# Sheet1.net
KiCad netlist of a schematic drawn in Altium Designer
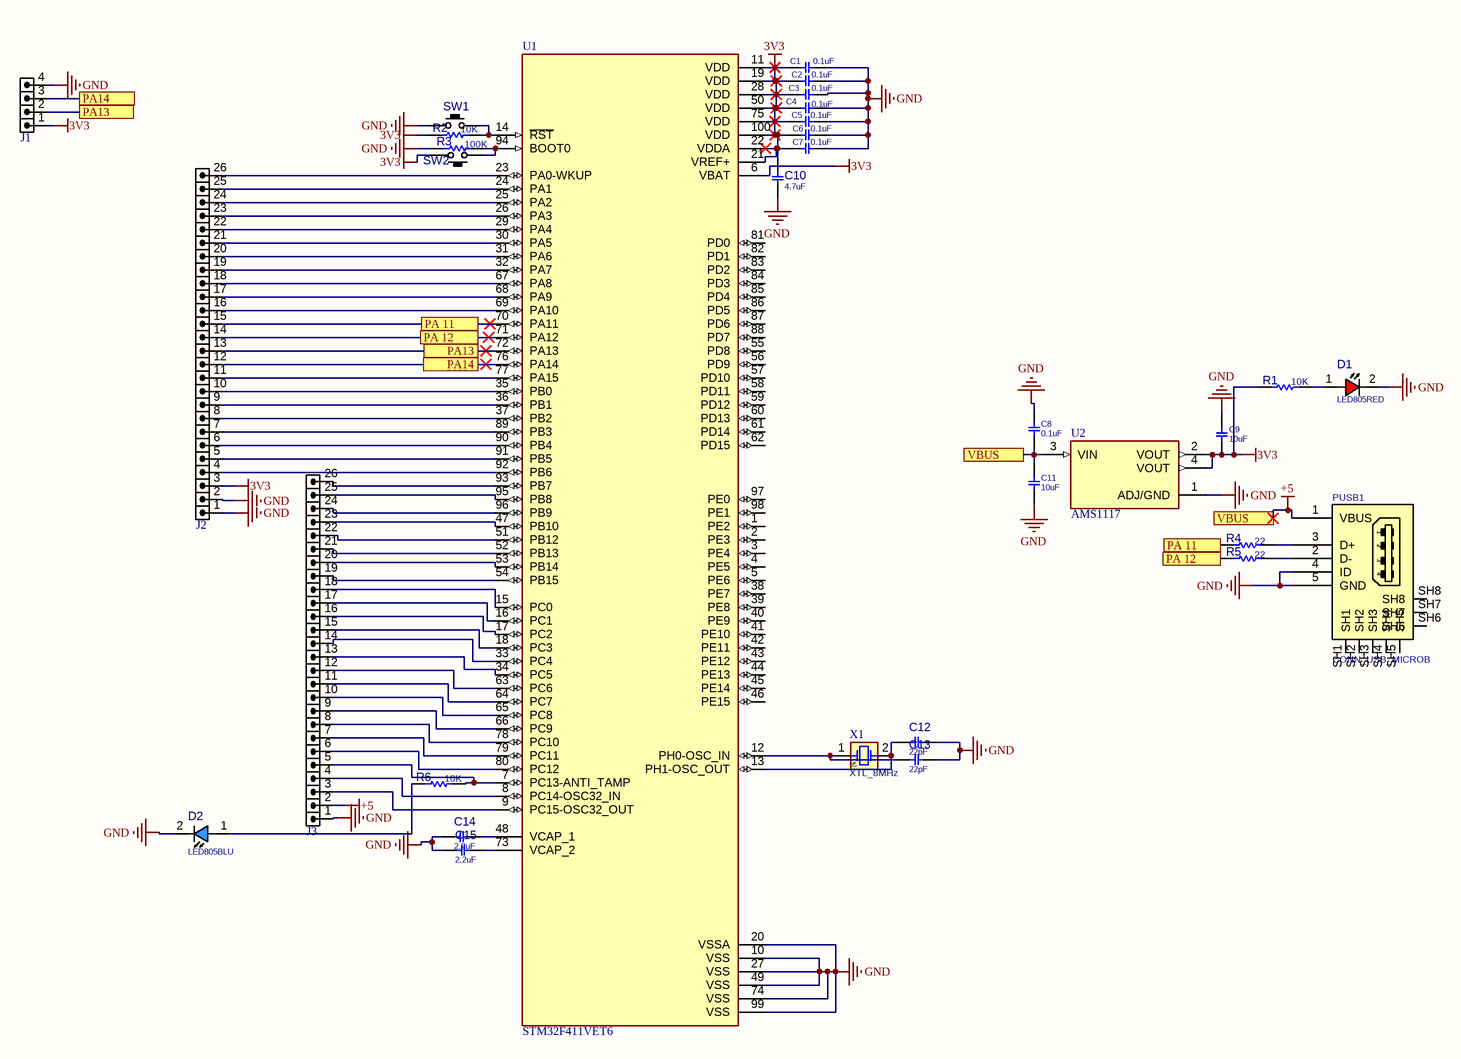
[diagram p0: Sheet1.SchDoc]

(export (version "E")
  (design (tool "Eeschema 10.0.6"))
  (components
    (comp (ref "C1")
      (value "0.1uF")
      (footprint "C0402")
      (description "CAP, MLCC, 100nF, 50V, X5R, 10%, 0402C")
      (fields (field (name "MANF_P#") "UMK105BJ104KV-F") (field (name "MANF") "Taiyo Yuden"))
      (libsource (lib "Custom") (part "CAP_SMD_MLCC_100n50T"))
    )
    (comp (ref "C2")
      (value "0.1uF")
      (footprint "C0402")
      (description "CAP, MLCC, 100nF, 50V, X5R, 10%, 0402C")
      (fields (field (name "MANF_P#") "UMK105BJ104KV-F") (field (name "MANF") "Taiyo Yuden"))
      (libsource (lib "Custom") (part "CAP_SMD_MLCC_100n50T"))
    )
    (comp (ref "C3")
      (value "0.1uF")
      (footprint "C0402")
      (description "CAP, MLCC, 100nF, 50V, X5R, 10%, 0402C")
      (fields (field (name "MANF_P#") "UMK105BJ104KV-F") (field (name "MANF") "Taiyo Yuden"))
      (libsource (lib "Custom") (part "CAP_SMD_MLCC_100n50T"))
    )
    (comp (ref "C4")
      (value "0.1uF")
      (footprint "C0402")
      (description "CAP, MLCC, 100nF, 50V, X5R, 10%, 0402C")
      (fields (field (name "MANF_P#") "UMK105BJ104KV-F") (field (name "MANF") "Taiyo Yuden"))
      (libsource (lib "Custom") (part "CAP_SMD_MLCC_100n50T"))
    )
    (comp (ref "C5")
      (value "0.1uF")
      (footprint "C0402")
      (description "CAP, MLCC, 100nF, 50V, X5R, 10%, 0402C")
      (fields (field (name "MANF_P#") "UMK105BJ104KV-F") (field (name "MANF") "Taiyo Yuden"))
      (libsource (lib "Custom") (part "CAP_SMD_MLCC_100n50T"))
    )
    (comp (ref "C6")
      (value "0.1uF")
      (footprint "C0402")
      (description "CAP, MLCC, 100nF, 50V, X5R, 10%, 0402C")
      (fields (field (name "MANF_P#") "UMK105BJ104KV-F") (field (name "MANF") "Taiyo Yuden"))
      (libsource (lib "Custom") (part "CAP_SMD_MLCC_100n50T"))
    )
    (comp (ref "C7")
      (value "0.1uF")
      (footprint "C0402")
      (description "CAP, MLCC, 100nF, 50V, X5R, 10%, 0402C")
      (fields (field (name "MANF_P#") "UMK105BJ104KV-F") (field (name "MANF") "Taiyo Yuden"))
      (libsource (lib "Custom") (part "CAP_SMD_MLCC_100n50T"))
    )
    (comp (ref "C8")
      (value "0.1uF")
      (footprint "C0402")
      (description "CAP, MLCC, 100nF, 50V, X5R, 10%, 0402C")
      (fields (field (name "MANF_P#") "UMK105BJ104KV-F") (field (name "MANF") "Taiyo Yuden"))
      (libsource (lib "Custom") (part "CAP_SMD_MLCC_100n50T"))
    )
    (comp (ref "C9")
      (value "10uF")
      (footprint "C0805")
      (description "CAP, MLCC, X5R 10uF 10% 25V 0805")
      (fields (field (name "MANF_P#") "TMK212BBJ106MG") (field (name "MANF") "Taiyo Yuden"))
      (libsource (lib "Custom") (part "CAP_SMD_MLCC_10u25V"))
    )
    (comp (ref "C10")
      (value "4.7uF")
      (footprint "C1206")
      (description "CAP, MLCC, SMD")
      (fields (field (name "MANF_P#") "UMK316BJ475KL-T") (field (name "MANF") "Taiyo Yuden"))
      (libsource (lib "Custom") (part "CAP_SMD_MLCC_4.7u50V"))
    )
    (comp (ref "C11")
      (value "10uF")
      (footprint "C0805")
      (description "CAP, MLCC, X5R 10uF 10% 25V 0805")
      (fields (field (name "MANF_P#") "TMK212BBJ106MG") (field (name "MANF") "Taiyo Yuden"))
      (libsource (lib "Custom") (part "CAP_SMD_MLCC_10u25V"))
    )
    (comp (ref "C12")
      (value "22pF")
      (footprint "C0402")
      (description "CAP, MLCC, 50V, C0G, 2%")
      (fields (field (name "MANF_P#") "GRM1555C1H220GA01D") (field (name "MANF") "MURATA"))
      (libsource (lib "Custom") (part "CAP_SMD_MLCC_22p50V"))
    )
    (comp (ref "C13")
      (value "22pF")
      (footprint "C0402")
      (description "CAP, MLCC, 50V, C0G, 2%")
      (fields (field (name "MANF_P#") "GRM1555C1H220GA01D") (field (name "MANF") "MURATA"))
      (libsource (lib "Custom") (part "CAP_SMD_MLCC_22p50V"))
    )
    (comp (ref "C14")
      (value "2.2uF")
      (footprint "C0805")
      (description "CAP, MLCC")
      (fields (field (name "MANF_P#") "UMK212ABJ225KG-T") (field (name "MANF") "Taiyo Yuden"))
      (libsource (lib "Custom") (part "CAP_SMD_MLCC_2.2u50V_0805"))
    )
    (comp (ref "C15")
      (value "2.2uF")
      (footprint "C0805")
      (description "CAP, MLCC")
      (fields (field (name "MANF_P#") "UMK212ABJ225KG-T") (field (name "MANF") "Taiyo Yuden"))
      (libsource (lib "Custom") (part "CAP_SMD_MLCC_2.2u50V_0805"))
    )
    (comp (ref "D1")
      (value "LED805RED")
      (footprint "LED0805RED")
      (description "LED, SMD, 0805, RED")
      (fields (field (name "MANF") "MANF") (field (name "MANF_P#") "MANF_PART#"))
      (libsource (lib "Custom") (part "LED_SMD_0805_RED"))
    )
    (comp (ref "D2")
      (value "LED805BLU")
      (footprint "LED0805BLU")
      (description "LED, SMD, 0805, BLUE")
      (fields (field (name "MANF") "MANF") (field (name "MANF_P#") "MANF_PART#"))
      (libsource (lib "Custom") (part "LED_SMD_0805_BLU"))
    )
    (comp (ref "J1")
      (value "HDR1X4")
      (footprint "HDRR_M_1X4")
      (description "CONN, HEADER, RightAngle, Male, pitch: 2.54mm, 4POS")
      (libsource (lib "Custom") (part "HDRR_M_1X4"))
    )
    (comp (ref "J2")
      (value "HDRF26")
      (footprint "HDR_M_1X26")
      (description "CONN, HEADER, Male, pitch: 2.54mm, 26POS")
      (libsource (lib "Custom") (part "HDR_M_1X26"))
    )
    (comp (ref "J3")
      (value "HDRF26")
      (footprint "HDR_M_1X26")
      (description "CONN, HEADER, Male, pitch: 2.54mm, 26POS")
      (libsource (lib "Custom") (part "HDR_M_1X26"))
    )
    (comp (ref "PUSB1")
      (value "CONN_USB_MICROB")
      (footprint "USB_MICRO_B_BM_SHT")
      (description "CONN, USB, MICRO B, R/A, SMD, BOTTOM MOUNT, SHT")
      (libsource (lib "Custom") (part "CONN_USB_MICRO_B_BM_SHT"))
    )
    (comp (ref "R1")
      (value "10K")
      (footprint "R0603")
      (description "RESISTOR, SMD")
      (libsource (lib "Custom") (part "RES_SMD_0603"))
    )
    (comp (ref "R2")
      (value "10K")
      (footprint "R0603")
      (description "RESISTOR, SMD")
      (libsource (lib "Custom") (part "RES_SMD_0603"))
    )
    (comp (ref "R3")
      (value "100K")
      (footprint "R0603")
      (description "RESISTOR, SMD")
      (libsource (lib "Custom") (part "RES_SMD_0603"))
    )
    (comp (ref "R4")
      (value "22")
      (footprint "R0603")
      (description "RESISTOR, SMD")
      (libsource (lib "Custom") (part "RES_SMD_0603"))
    )
    (comp (ref "R5")
      (value "22")
      (footprint "R0603")
      (description "RESISTOR, SMD")
      (libsource (lib "Custom") (part "RES_SMD_0603"))
    )
    (comp (ref "R6")
      (value "10K")
      (footprint "R0603")
      (description "RESISTOR, SMD")
      (libsource (lib "Custom") (part "RES_SMD_0603"))
    )
    (comp (ref "SW1")
      (value "PUSHBUTTON")
      (footprint "SWPBT_SPST_6X6X4")
      (description "SWITCH, PUSH BUTTON, TACTILE, THD, SPST, 6X6X4mm")
      (libsource (lib "") (part "SWPBT_SPST_6X6X4_1"))
    )
    (comp (ref "SW2")
      (value "PUSHBUTTON")
      (footprint "SWPBT_SPST_6X6X4")
      (description "SWITCH, PUSH BUTTON, TACTILE, THD, SPST, 6X6X4mm")
      (libsource (lib "Custom") (part "SWPBT_SPST_6X6X4"))
    )
    (comp (ref "U1")
      (value "STM32F411VET6")
      (footprint "QFP50P1600X1600X160-100N")
      (fields (field (name "MF") "STMicroelectronics") (field (name "MP") "STM32F411VET6."))
      (libsource (lib "STM32F411VET6") (part "STM32F411VET6"))
    )
    (comp (ref "U2")
      (value "AMS1117")
      (footprint "SOT229P700X180-4N")
      (description "1A LOW DROPOUT VOLTAGE REGULATOR SOT-223")
      (fields (field (name "MF") "Advanced Monolithic Systems"))
      (libsource (lib "AMS1117") (part "AMS1117"))
    )
    (comp (ref "X1")
      (value "XTL_8MHz")
      (footprint "XTL_2_8045")
      (description "Crystal 2")
      (fields (field (name "MANF") "ABRACON") (field (name "MANF_P#") "ABM2-8.000MHZ-D4Y-T"))
      (libsource (lib "Custom") (part "XTL_2_8MHz_ABM2"))
    )
  )
  (nets
    (net (code "1") (name "+5") (class "Default")
      (node (ref "C11") (pin "2") (pinfunction "2_2") (pintype "passive"))
      (node (ref "C8") (pin "1") (pinfunction "1_1") (pintype "passive"))
      (node (ref "J3") (pin "2") (pinfunction "2_2") (pintype "passive"))
      (node (ref "PUSB1") (pin "1") (pinfunction "VBUS_1") (pintype "power_in"))
      (node (ref "U2") (pin "3") (pinfunction "VIN_3") (pintype "input"))
    )
    (net (code "2") (name "/PA 11") (class "Default")
      (node (ref "J2") (pin "15") (pinfunction "15_15") (pintype "passive"))
      (node (ref "R4") (pin "1") (pinfunction "1_1") (pintype "passive"))
      (node (ref "U1") (pin "70") (pinfunction "PA11_70") (pintype "bidirectional"))
    )
    (net (code "3") (name "/PA 12") (class "Default")
      (node (ref "J2") (pin "14") (pinfunction "14_14") (pintype "passive"))
      (node (ref "R5") (pin "1") (pinfunction "1_1") (pintype "passive"))
      (node (ref "U1") (pin "71") (pinfunction "PA12_71") (pintype "bidirectional"))
    )
    (net (code "4") (name "/PA13") (class "Default")
      (node (ref "J1") (pin "2") (pinfunction "2_2") (pintype "passive"))
      (node (ref "J2") (pin "13") (pinfunction "13_13") (pintype "passive"))
      (node (ref "U1") (pin "72") (pinfunction "PA13_72") (pintype "bidirectional"))
    )
    (net (code "5") (name "/PA14") (class "Default")
      (node (ref "J1") (pin "3") (pinfunction "3_3") (pintype "passive"))
      (node (ref "J2") (pin "12") (pinfunction "12_12") (pintype "passive"))
      (node (ref "U1") (pin "76") (pinfunction "PA14_76") (pintype "bidirectional"))
    )
    (net (code "6") (name "3V3") (class "Default")
      (node (ref "C1") (pin "1") (pinfunction "1_1") (pintype "passive"))
      (node (ref "C10") (pin "2") (pinfunction "2_2") (pintype "passive"))
      (node (ref "C2") (pin "1") (pinfunction "1_1") (pintype "passive"))
      (node (ref "C3") (pin "1") (pinfunction "1_1") (pintype "passive"))
      (node (ref "C4") (pin "1") (pinfunction "1_1") (pintype "passive"))
      (node (ref "C5") (pin "1") (pinfunction "1_1") (pintype "passive"))
      (node (ref "C6") (pin "1") (pinfunction "1_1") (pintype "passive"))
      (node (ref "C7") (pin "1") (pinfunction "1_1") (pintype "passive"))
      (node (ref "C9") (pin "2") (pinfunction "2_2") (pintype "passive"))
      (node (ref "J1") (pin "1") (pinfunction "1_1") (pintype "passive"))
      (node (ref "J2") (pin "3") (pinfunction "3_3") (pintype "passive"))
      (node (ref "R1") (pin "1") (pinfunction "1_1") (pintype "passive"))
      (node (ref "R2") (pin "1") (pinfunction "1_1") (pintype "passive"))
      (node (ref "SW2") (pin "2") (pinfunction "2_2") (pintype "passive"))
      (node (ref "U1") (pin "100") (pinfunction "VDD_100") (pintype "power_in"))
      (node (ref "U1") (pin "11") (pinfunction "VDD_11") (pintype "power_in"))
      (node (ref "U1") (pin "19") (pinfunction "VDD_19") (pintype "power_in"))
      (node (ref "U1") (pin "21") (pinfunction "VREF+_21") (pintype "power_in"))
      (node (ref "U1") (pin "22") (pinfunction "VDDA_22") (pintype "power_in"))
      (node (ref "U1") (pin "28") (pinfunction "VDD_28") (pintype "power_in"))
      (node (ref "U1") (pin "50") (pinfunction "VDD_50") (pintype "power_in"))
      (node (ref "U1") (pin "6") (pinfunction "VBAT_6") (pintype "power_in"))
      (node (ref "U1") (pin "75") (pinfunction "VDD_75") (pintype "power_in"))
      (node (ref "U2") (pin "2") (pinfunction "VOUT_2") (pintype "output"))
      (node (ref "U2") (pin "4") (pinfunction "VOUT_4") (pintype "output"))
    )
    (net (code "7") (name "GND") (class "Default")
      (node (ref "C1") (pin "2") (pinfunction "2_2") (pintype "passive"))
      (node (ref "C10") (pin "1") (pinfunction "1_1") (pintype "passive"))
      (node (ref "C11") (pin "1") (pinfunction "1_1") (pintype "passive"))
      (node (ref "C12") (pin "1") (pinfunction "1_1") (pintype "passive"))
      (node (ref "C13") (pin "1") (pinfunction "1_1") (pintype "passive"))
      (node (ref "C14") (pin "1") (pinfunction "1_1") (pintype "passive"))
      (node (ref "C15") (pin "1") (pinfunction "1_1") (pintype "passive"))
      (node (ref "C2") (pin "2") (pinfunction "2_2") (pintype "passive"))
      (node (ref "C3") (pin "2") (pinfunction "2_2") (pintype "passive"))
      (node (ref "C4") (pin "2") (pinfunction "2_2") (pintype "passive"))
      (node (ref "C5") (pin "2") (pinfunction "2_2") (pintype "passive"))
      (node (ref "C6") (pin "2") (pinfunction "2_2") (pintype "passive"))
      (node (ref "C7") (pin "2") (pinfunction "2_2") (pintype "passive"))
      (node (ref "C8") (pin "2") (pinfunction "2_2") (pintype "passive"))
      (node (ref "C9") (pin "1") (pinfunction "1_1") (pintype "passive"))
      (node (ref "D1") (pin "2") (pinfunction "CATHODE_2") (pintype "passive"))
      (node (ref "D2") (pin "2") (pinfunction "CATHODE_2") (pintype "passive"))
      (node (ref "J1") (pin "4") (pinfunction "4_4") (pintype "passive"))
      (node (ref "J2") (pin "1") (pinfunction "1_1") (pintype "passive"))
      (node (ref "J2") (pin "2") (pinfunction "2_2") (pintype "passive"))
      (node (ref "J3") (pin "1") (pinfunction "1_1") (pintype "passive"))
      (node (ref "PUSB1") (pin "4") (pinfunction "ID_4") (pintype "power_in"))
      (node (ref "PUSB1") (pin "5") (pinfunction "GND_5") (pintype "power_in"))
      (node (ref "R3") (pin "1") (pinfunction "1_1") (pintype "passive"))
      (node (ref "SW1") (pin "1") (pinfunction "1_1") (pintype "passive"))
      (node (ref "U1") (pin "10") (pinfunction "VSS_10") (pintype "power_in"))
      (node (ref "U1") (pin "20") (pinfunction "VSSA_20") (pintype "power_in"))
      (node (ref "U1") (pin "27") (pinfunction "VSS_27") (pintype "power_in"))
      (node (ref "U1") (pin "49") (pinfunction "VSS_49") (pintype "power_in"))
      (node (ref "U1") (pin "74") (pinfunction "VSS_74") (pintype "power_in"))
      (node (ref "U1") (pin "99") (pinfunction "VSS_99") (pintype "power_in"))
      (node (ref "U2") (pin "1") (pinfunction "ADJ/GND_1") (pintype "power_in"))
    )
    (net (code "8") (name "Net-(D1-ANODE)") (class "Default")
      (node (ref "D1") (pin "1") (pinfunction "ANODE_1") (pintype "passive"))
      (node (ref "R1") (pin "2") (pinfunction "2_2") (pintype "passive"))
    )
    (net (code "9") (name "Net-(D2-ANODE)") (class "Default")
      (node (ref "D2") (pin "1") (pinfunction "ANODE_1") (pintype "passive"))
      (node (ref "R6") (pin "1") (pinfunction "1_1") (pintype "passive"))
    )
    (net (code "10") (name "Net-(PUSB1-D+)") (class "Default")
      (node (ref "PUSB1") (pin "3") (pinfunction "D+_3") (pintype "passive"))
      (node (ref "R4") (pin "2") (pinfunction "2_2") (pintype "passive"))
    )
    (net (code "11") (name "Net-(PUSB1-D-)") (class "Default")
      (node (ref "PUSB1") (pin "2") (pinfunction "D-_2") (pintype "passive"))
      (node (ref "R5") (pin "2") (pinfunction "2_2") (pintype "passive"))
    )
    (net (code "12") (name "Net-(U1-BOOT0)") (class "Default")
      (node (ref "R3") (pin "2") (pinfunction "2_2") (pintype "passive"))
      (node (ref "SW2") (pin "1") (pinfunction "1_1") (pintype "passive"))
      (node (ref "U1") (pin "94") (pinfunction "BOOT0_94") (pintype "input"))
    )
    (net (code "13") (name "Net-(U1-PA0-WKUP)") (class "Default")
      (node (ref "J2") (pin "26") (pinfunction "26_26") (pintype "passive"))
      (node (ref "U1") (pin "23") (pinfunction "PA0-WKUP_23") (pintype "bidirectional"))
    )
    (net (code "14") (name "Net-(U1-PA1)") (class "Default")
      (node (ref "J2") (pin "25") (pinfunction "25_25") (pintype "passive"))
      (node (ref "U1") (pin "24") (pinfunction "PA1_24") (pintype "bidirectional"))
    )
    (net (code "15") (name "Net-(U1-PA2)") (class "Default")
      (node (ref "J2") (pin "24") (pinfunction "24_24") (pintype "passive"))
      (node (ref "U1") (pin "25") (pinfunction "PA2_25") (pintype "bidirectional"))
    )
    (net (code "16") (name "Net-(U1-PA3)") (class "Default")
      (node (ref "J2") (pin "23") (pinfunction "23_23") (pintype "passive"))
      (node (ref "U1") (pin "26") (pinfunction "PA3_26") (pintype "bidirectional"))
    )
    (net (code "17") (name "Net-(U1-PA4)") (class "Default")
      (node (ref "J2") (pin "22") (pinfunction "22_22") (pintype "passive"))
      (node (ref "U1") (pin "29") (pinfunction "PA4_29") (pintype "bidirectional"))
    )
    (net (code "18") (name "Net-(U1-PA5)") (class "Default")
      (node (ref "J2") (pin "21") (pinfunction "21_21") (pintype "passive"))
      (node (ref "U1") (pin "30") (pinfunction "PA5_30") (pintype "bidirectional"))
    )
    (net (code "19") (name "Net-(U1-PA6)") (class "Default")
      (node (ref "J2") (pin "20") (pinfunction "20_20") (pintype "passive"))
      (node (ref "U1") (pin "31") (pinfunction "PA6_31") (pintype "bidirectional"))
    )
    (net (code "20") (name "Net-(U1-PA7)") (class "Default")
      (node (ref "J2") (pin "19") (pinfunction "19_19") (pintype "passive"))
      (node (ref "U1") (pin "32") (pinfunction "PA7_32") (pintype "bidirectional"))
    )
    (net (code "21") (name "Net-(U1-PA8)") (class "Default")
      (node (ref "J2") (pin "18") (pinfunction "18_18") (pintype "passive"))
      (node (ref "U1") (pin "67") (pinfunction "PA8_67") (pintype "bidirectional"))
    )
    (net (code "22") (name "Net-(U1-PA9)") (class "Default")
      (node (ref "J2") (pin "17") (pinfunction "17_17") (pintype "passive"))
      (node (ref "U1") (pin "68") (pinfunction "PA9_68") (pintype "bidirectional"))
    )
    (net (code "23") (name "Net-(U1-PA10)") (class "Default")
      (node (ref "J2") (pin "16") (pinfunction "16_16") (pintype "passive"))
      (node (ref "U1") (pin "69") (pinfunction "PA10_69") (pintype "bidirectional"))
    )
    (net (code "24") (name "Net-(U1-PA15)") (class "Default")
      (node (ref "J2") (pin "11") (pinfunction "11_11") (pintype "passive"))
      (node (ref "U1") (pin "77") (pinfunction "PA15_77") (pintype "bidirectional"))
    )
    (net (code "25") (name "Net-(U1-PB0)") (class "Default")
      (node (ref "J2") (pin "10") (pinfunction "10_10") (pintype "passive"))
      (node (ref "U1") (pin "35") (pinfunction "PB0_35") (pintype "bidirectional"))
    )
    (net (code "26") (name "Net-(U1-PB1)") (class "Default")
      (node (ref "J2") (pin "9") (pinfunction "9_9") (pintype "passive"))
      (node (ref "U1") (pin "36") (pinfunction "PB1_36") (pintype "bidirectional"))
    )
    (net (code "27") (name "Net-(U1-PB2)") (class "Default")
      (node (ref "J2") (pin "8") (pinfunction "8_8") (pintype "passive"))
      (node (ref "U1") (pin "37") (pinfunction "PB2_37") (pintype "bidirectional"))
    )
    (net (code "28") (name "Net-(U1-PB3)") (class "Default")
      (node (ref "J2") (pin "7") (pinfunction "7_7") (pintype "passive"))
      (node (ref "U1") (pin "89") (pinfunction "PB3_89") (pintype "bidirectional"))
    )
    (net (code "29") (name "Net-(U1-PB4)") (class "Default")
      (node (ref "J2") (pin "6") (pinfunction "6_6") (pintype "passive"))
      (node (ref "U1") (pin "90") (pinfunction "PB4_90") (pintype "bidirectional"))
    )
    (net (code "30") (name "Net-(U1-PB5)") (class "Default")
      (node (ref "J2") (pin "5") (pinfunction "5_5") (pintype "passive"))
      (node (ref "U1") (pin "91") (pinfunction "PB5_91") (pintype "bidirectional"))
    )
    (net (code "31") (name "Net-(U1-PB6)") (class "Default")
      (node (ref "J2") (pin "4") (pinfunction "4_4") (pintype "passive"))
      (node (ref "U1") (pin "92") (pinfunction "PB6_92") (pintype "bidirectional"))
    )
    (net (code "32") (name "Net-(U1-PB7)") (class "Default")
      (node (ref "J3") (pin "26") (pinfunction "26_26") (pintype "passive"))
      (node (ref "U1") (pin "93") (pinfunction "PB7_93") (pintype "bidirectional"))
    )
    (net (code "33") (name "Net-(U1-PB8)") (class "Default")
      (node (ref "J3") (pin "25") (pinfunction "25_25") (pintype "passive"))
      (node (ref "U1") (pin "95") (pinfunction "PB8_95") (pintype "bidirectional"))
    )
    (net (code "34") (name "Net-(U1-PB9)") (class "Default")
      (node (ref "J3") (pin "24") (pinfunction "24_24") (pintype "passive"))
      (node (ref "U1") (pin "96") (pinfunction "PB9_96") (pintype "bidirectional"))
    )
    (net (code "35") (name "Net-(U1-PB10)") (class "Default")
      (node (ref "J3") (pin "23") (pinfunction "23_23") (pintype "passive"))
      (node (ref "U1") (pin "47") (pinfunction "PB10_47") (pintype "bidirectional"))
    )
    (net (code "36") (name "Net-(U1-PB12)") (class "Default")
      (node (ref "J3") (pin "22") (pinfunction "22_22") (pintype "passive"))
      (node (ref "U1") (pin "51") (pinfunction "PB12_51") (pintype "bidirectional"))
    )
    (net (code "37") (name "Net-(U1-PB13)") (class "Default")
      (node (ref "J3") (pin "21") (pinfunction "21_21") (pintype "passive"))
      (node (ref "U1") (pin "52") (pinfunction "PB13_52") (pintype "bidirectional"))
    )
    (net (code "38") (name "Net-(U1-PB14)") (class "Default")
      (node (ref "J3") (pin "20") (pinfunction "20_20") (pintype "passive"))
      (node (ref "U1") (pin "53") (pinfunction "PB14_53") (pintype "bidirectional"))
    )
    (net (code "39") (name "Net-(U1-PB15)") (class "Default")
      (node (ref "J3") (pin "19") (pinfunction "19_19") (pintype "passive"))
      (node (ref "U1") (pin "54") (pinfunction "PB15_54") (pintype "bidirectional"))
    )
    (net (code "40") (name "Net-(U1-PC0)") (class "Default")
      (node (ref "J3") (pin "18") (pinfunction "18_18") (pintype "passive"))
      (node (ref "U1") (pin "15") (pinfunction "PC0_15") (pintype "bidirectional"))
    )
    (net (code "41") (name "Net-(U1-PC1)") (class "Default")
      (node (ref "J3") (pin "17") (pinfunction "17_17") (pintype "passive"))
      (node (ref "U1") (pin "16") (pinfunction "PC1_16") (pintype "bidirectional"))
    )
    (net (code "42") (name "Net-(U1-PC2)") (class "Default")
      (node (ref "J3") (pin "16") (pinfunction "16_16") (pintype "passive"))
      (node (ref "U1") (pin "17") (pinfunction "PC2_17") (pintype "bidirectional"))
    )
    (net (code "43") (name "Net-(U1-PC3)") (class "Default")
      (node (ref "J3") (pin "15") (pinfunction "15_15") (pintype "passive"))
      (node (ref "U1") (pin "18") (pinfunction "PC3_18") (pintype "bidirectional"))
    )
    (net (code "44") (name "Net-(U1-PC4)") (class "Default")
      (node (ref "J3") (pin "14") (pinfunction "14_14") (pintype "passive"))
      (node (ref "U1") (pin "33") (pinfunction "PC4_33") (pintype "bidirectional"))
    )
    (net (code "45") (name "Net-(U1-PC5)") (class "Default")
      (node (ref "J3") (pin "13") (pinfunction "13_13") (pintype "passive"))
      (node (ref "U1") (pin "34") (pinfunction "PC5_34") (pintype "bidirectional"))
    )
    (net (code "46") (name "Net-(U1-PC6)") (class "Default")
      (node (ref "J3") (pin "12") (pinfunction "12_12") (pintype "passive"))
      (node (ref "U1") (pin "63") (pinfunction "PC6_63") (pintype "bidirectional"))
    )
    (net (code "47") (name "Net-(U1-PC7)") (class "Default")
      (node (ref "J3") (pin "11") (pinfunction "11_11") (pintype "passive"))
      (node (ref "U1") (pin "64") (pinfunction "PC7_64") (pintype "bidirectional"))
    )
    (net (code "48") (name "Net-(U1-PC8)") (class "Default")
      (node (ref "J3") (pin "10") (pinfunction "10_10") (pintype "passive"))
      (node (ref "U1") (pin "65") (pinfunction "PC8_65") (pintype "bidirectional"))
    )
    (net (code "49") (name "Net-(U1-PC9)") (class "Default")
      (node (ref "J3") (pin "9") (pinfunction "9_9") (pintype "passive"))
      (node (ref "U1") (pin "66") (pinfunction "PC9_66") (pintype "bidirectional"))
    )
    (net (code "50") (name "Net-(U1-PC10)") (class "Default")
      (node (ref "J3") (pin "8") (pinfunction "8_8") (pintype "passive"))
      (node (ref "U1") (pin "78") (pinfunction "PC10_78") (pintype "bidirectional"))
    )
    (net (code "51") (name "Net-(U1-PC11)") (class "Default")
      (node (ref "J3") (pin "7") (pinfunction "7_7") (pintype "passive"))
      (node (ref "U1") (pin "79") (pinfunction "PC11_79") (pintype "bidirectional"))
    )
    (net (code "52") (name "Net-(U1-PC12)") (class "Default")
      (node (ref "J3") (pin "6") (pinfunction "6_6") (pintype "passive"))
      (node (ref "U1") (pin "80") (pinfunction "PC12_80") (pintype "bidirectional"))
    )
    (net (code "53") (name "Net-(U1-PC13-ANTI_TAMP)") (class "Default")
      (node (ref "J3") (pin "5") (pinfunction "5_5") (pintype "passive"))
      (node (ref "R6") (pin "2") (pinfunction "2_2") (pintype "passive"))
      (node (ref "U1") (pin "7") (pinfunction "PC13-ANTI_TAMP_7") (pintype "bidirectional"))
    )
    (net (code "54") (name "Net-(U1-PC14-OSC32_IN)") (class "Default")
      (node (ref "J3") (pin "4") (pinfunction "4_4") (pintype "passive"))
      (node (ref "U1") (pin "8") (pinfunction "PC14-OSC32_IN_8") (pintype "bidirectional"))
    )
    (net (code "55") (name "Net-(U1-PC15-OSC32_OUT)") (class "Default")
      (node (ref "J3") (pin "3") (pinfunction "3_3") (pintype "passive"))
      (node (ref "U1") (pin "9") (pinfunction "PC15-OSC32_OUT_9") (pintype "bidirectional"))
    )
    (net (code "56") (name "Net-(U1-PH0-OSC_IN)") (class "Default")
      (node (ref "C13") (pin "2") (pinfunction "2_2") (pintype "passive"))
      (node (ref "U1") (pin "12") (pinfunction "PH0-OSC_IN_12") (pintype "bidirectional"))
      (node (ref "X1") (pin "1") (pinfunction "OSC1_1") (pintype "passive"))
    )
    (net (code "57") (name "Net-(U1-PH1-OSC_OUT)") (class "Default")
      (node (ref "C12") (pin "2") (pinfunction "2_2") (pintype "passive"))
      (node (ref "U1") (pin "13") (pinfunction "PH1-OSC_OUT_13") (pintype "bidirectional"))
      (node (ref "X1") (pin "2") (pinfunction "OSC2_2") (pintype "passive"))
    )
    (net (code "58") (name "Net-(U1-VCAP_1)") (class "Default")
      (node (ref "C14") (pin "2") (pinfunction "2_2") (pintype "passive"))
      (node (ref "U1") (pin "48") (pinfunction "VCAP_1_48") (pintype "passive"))
    )
    (net (code "59") (name "Net-(U1-VCAP_2)") (class "Default")
      (node (ref "C15") (pin "2") (pinfunction "2_2") (pintype "passive"))
      (node (ref "U1") (pin "73") (pinfunction "VCAP_2_73") (pintype "passive"))
    )
    (net (code "60") (name "Net-(U1-~{RST})") (class "Default")
      (node (ref "R2") (pin "2") (pinfunction "2_2") (pintype "passive"))
      (node (ref "SW1") (pin "2") (pinfunction "2_2") (pintype "passive"))
      (node (ref "U1") (pin "14") (pinfunction "~{RST}_14") (pintype "input"))
    )
    (net (code "61") (name "unconnected-(PUSB1-PadSH1)") (class "Default")
      (node (ref "PUSB1") (pin "SH1") (pinfunction "SH1_SH1") (pintype "passive"))
    )
    (net (code "62") (name "unconnected-(PUSB1-PadSH2)") (class "Default")
      (node (ref "PUSB1") (pin "SH2") (pinfunction "SH2_SH2") (pintype "passive"))
    )
    (net (code "63") (name "unconnected-(PUSB1-PadSH3)") (class "Default")
      (node (ref "PUSB1") (pin "SH3") (pinfunction "SH3_SH3") (pintype "passive"))
    )
    (net (code "64") (name "unconnected-(PUSB1-PadSH4)") (class "Default")
      (node (ref "PUSB1") (pin "SH4") (pinfunction "SH4_SH4") (pintype "passive"))
    )
    (net (code "65") (name "unconnected-(PUSB1-PadSH5)") (class "Default")
      (node (ref "PUSB1") (pin "SH5") (pinfunction "SH5_SH5") (pintype "passive"))
    )
    (net (code "66") (name "unconnected-(PUSB1-PadSH6)") (class "Default")
      (node (ref "PUSB1") (pin "SH6") (pinfunction "SH6_SH6") (pintype "passive"))
    )
    (net (code "67") (name "unconnected-(PUSB1-PadSH7)") (class "Default")
      (node (ref "PUSB1") (pin "SH7") (pinfunction "SH7_SH7") (pintype "passive"))
    )
    (net (code "68") (name "unconnected-(PUSB1-PadSH8)") (class "Default")
      (node (ref "PUSB1") (pin "SH8") (pinfunction "SH8_SH8") (pintype "passive"))
    )
    (net (code "69") (name "unconnected-(U1-PD0-Pad81)") (class "Default")
      (node (ref "U1") (pin "81") (pinfunction "PD0_81") (pintype "bidirectional"))
    )
    (net (code "70") (name "unconnected-(U1-PD1-Pad82)") (class "Default")
      (node (ref "U1") (pin "82") (pinfunction "PD1_82") (pintype "bidirectional"))
    )
    (net (code "71") (name "unconnected-(U1-PD2-Pad83)") (class "Default")
      (node (ref "U1") (pin "83") (pinfunction "PD2_83") (pintype "bidirectional"))
    )
    (net (code "72") (name "unconnected-(U1-PD3-Pad84)") (class "Default")
      (node (ref "U1") (pin "84") (pinfunction "PD3_84") (pintype "bidirectional"))
    )
    (net (code "73") (name "unconnected-(U1-PD4-Pad85)") (class "Default")
      (node (ref "U1") (pin "85") (pinfunction "PD4_85") (pintype "bidirectional"))
    )
    (net (code "74") (name "unconnected-(U1-PD5-Pad86)") (class "Default")
      (node (ref "U1") (pin "86") (pinfunction "PD5_86") (pintype "bidirectional"))
    )
    (net (code "75") (name "unconnected-(U1-PD6-Pad87)") (class "Default")
      (node (ref "U1") (pin "87") (pinfunction "PD6_87") (pintype "bidirectional"))
    )
    (net (code "76") (name "unconnected-(U1-PD7-Pad88)") (class "Default")
      (node (ref "U1") (pin "88") (pinfunction "PD7_88") (pintype "bidirectional"))
    )
    (net (code "77") (name "unconnected-(U1-PD8-Pad55)") (class "Default")
      (node (ref "U1") (pin "55") (pinfunction "PD8_55") (pintype "bidirectional"))
    )
    (net (code "78") (name "unconnected-(U1-PD9-Pad56)") (class "Default")
      (node (ref "U1") (pin "56") (pinfunction "PD9_56") (pintype "bidirectional"))
    )
    (net (code "79") (name "unconnected-(U1-PD10-Pad57)") (class "Default")
      (node (ref "U1") (pin "57") (pinfunction "PD10_57") (pintype "bidirectional"))
    )
    (net (code "80") (name "unconnected-(U1-PD11-Pad58)") (class "Default")
      (node (ref "U1") (pin "58") (pinfunction "PD11_58") (pintype "bidirectional"))
    )
    (net (code "81") (name "unconnected-(U1-PD12-Pad59)") (class "Default")
      (node (ref "U1") (pin "59") (pinfunction "PD12_59") (pintype "bidirectional"))
    )
    (net (code "82") (name "unconnected-(U1-PD13-Pad60)") (class "Default")
      (node (ref "U1") (pin "60") (pinfunction "PD13_60") (pintype "bidirectional"))
    )
    (net (code "83") (name "unconnected-(U1-PD14-Pad61)") (class "Default")
      (node (ref "U1") (pin "61") (pinfunction "PD14_61") (pintype "bidirectional"))
    )
    (net (code "84") (name "unconnected-(U1-PD15-Pad62)") (class "Default")
      (node (ref "U1") (pin "62") (pinfunction "PD15_62") (pintype "bidirectional"))
    )
    (net (code "85") (name "unconnected-(U1-PE0-Pad97)") (class "Default")
      (node (ref "U1") (pin "97") (pinfunction "PE0_97") (pintype "bidirectional"))
    )
    (net (code "86") (name "unconnected-(U1-PE1-Pad98)") (class "Default")
      (node (ref "U1") (pin "98") (pinfunction "PE1_98") (pintype "bidirectional"))
    )
    (net (code "87") (name "unconnected-(U1-PE2-Pad1)") (class "Default")
      (node (ref "U1") (pin "1") (pinfunction "PE2_1") (pintype "bidirectional"))
    )
    (net (code "88") (name "unconnected-(U1-PE3-Pad2)") (class "Default")
      (node (ref "U1") (pin "2") (pinfunction "PE3_2") (pintype "bidirectional"))
    )
    (net (code "89") (name "unconnected-(U1-PE4-Pad3)") (class "Default")
      (node (ref "U1") (pin "3") (pinfunction "PE4_3") (pintype "bidirectional"))
    )
    (net (code "90") (name "unconnected-(U1-PE5-Pad4)") (class "Default")
      (node (ref "U1") (pin "4") (pinfunction "PE5_4") (pintype "bidirectional"))
    )
    (net (code "91") (name "unconnected-(U1-PE6-Pad5)") (class "Default")
      (node (ref "U1") (pin "5") (pinfunction "PE6_5") (pintype "bidirectional"))
    )
    (net (code "92") (name "unconnected-(U1-PE7-Pad38)") (class "Default")
      (node (ref "U1") (pin "38") (pinfunction "PE7_38") (pintype "bidirectional"))
    )
    (net (code "93") (name "unconnected-(U1-PE8-Pad39)") (class "Default")
      (node (ref "U1") (pin "39") (pinfunction "PE8_39") (pintype "bidirectional"))
    )
    (net (code "94") (name "unconnected-(U1-PE9-Pad40)") (class "Default")
      (node (ref "U1") (pin "40") (pinfunction "PE9_40") (pintype "bidirectional"))
    )
    (net (code "95") (name "unconnected-(U1-PE10-Pad41)") (class "Default")
      (node (ref "U1") (pin "41") (pinfunction "PE10_41") (pintype "bidirectional"))
    )
    (net (code "96") (name "unconnected-(U1-PE11-Pad42)") (class "Default")
      (node (ref "U1") (pin "42") (pinfunction "PE11_42") (pintype "bidirectional"))
    )
    (net (code "97") (name "unconnected-(U1-PE12-Pad43)") (class "Default")
      (node (ref "U1") (pin "43") (pinfunction "PE12_43") (pintype "bidirectional"))
    )
    (net (code "98") (name "unconnected-(U1-PE13-Pad44)") (class "Default")
      (node (ref "U1") (pin "44") (pinfunction "PE13_44") (pintype "bidirectional"))
    )
    (net (code "99") (name "unconnected-(U1-PE14-Pad45)") (class "Default")
      (node (ref "U1") (pin "45") (pinfunction "PE14_45") (pintype "bidirectional"))
    )
    (net (code "100") (name "unconnected-(U1-PE15-Pad46)") (class "Default")
      (node (ref "U1") (pin "46") (pinfunction "PE15_46") (pintype "bidirectional"))
    )
  )
)
